# SCH_SEEK-998-001_v1_00.net
KiCad netlist of a schematic drawn in EasyEDA
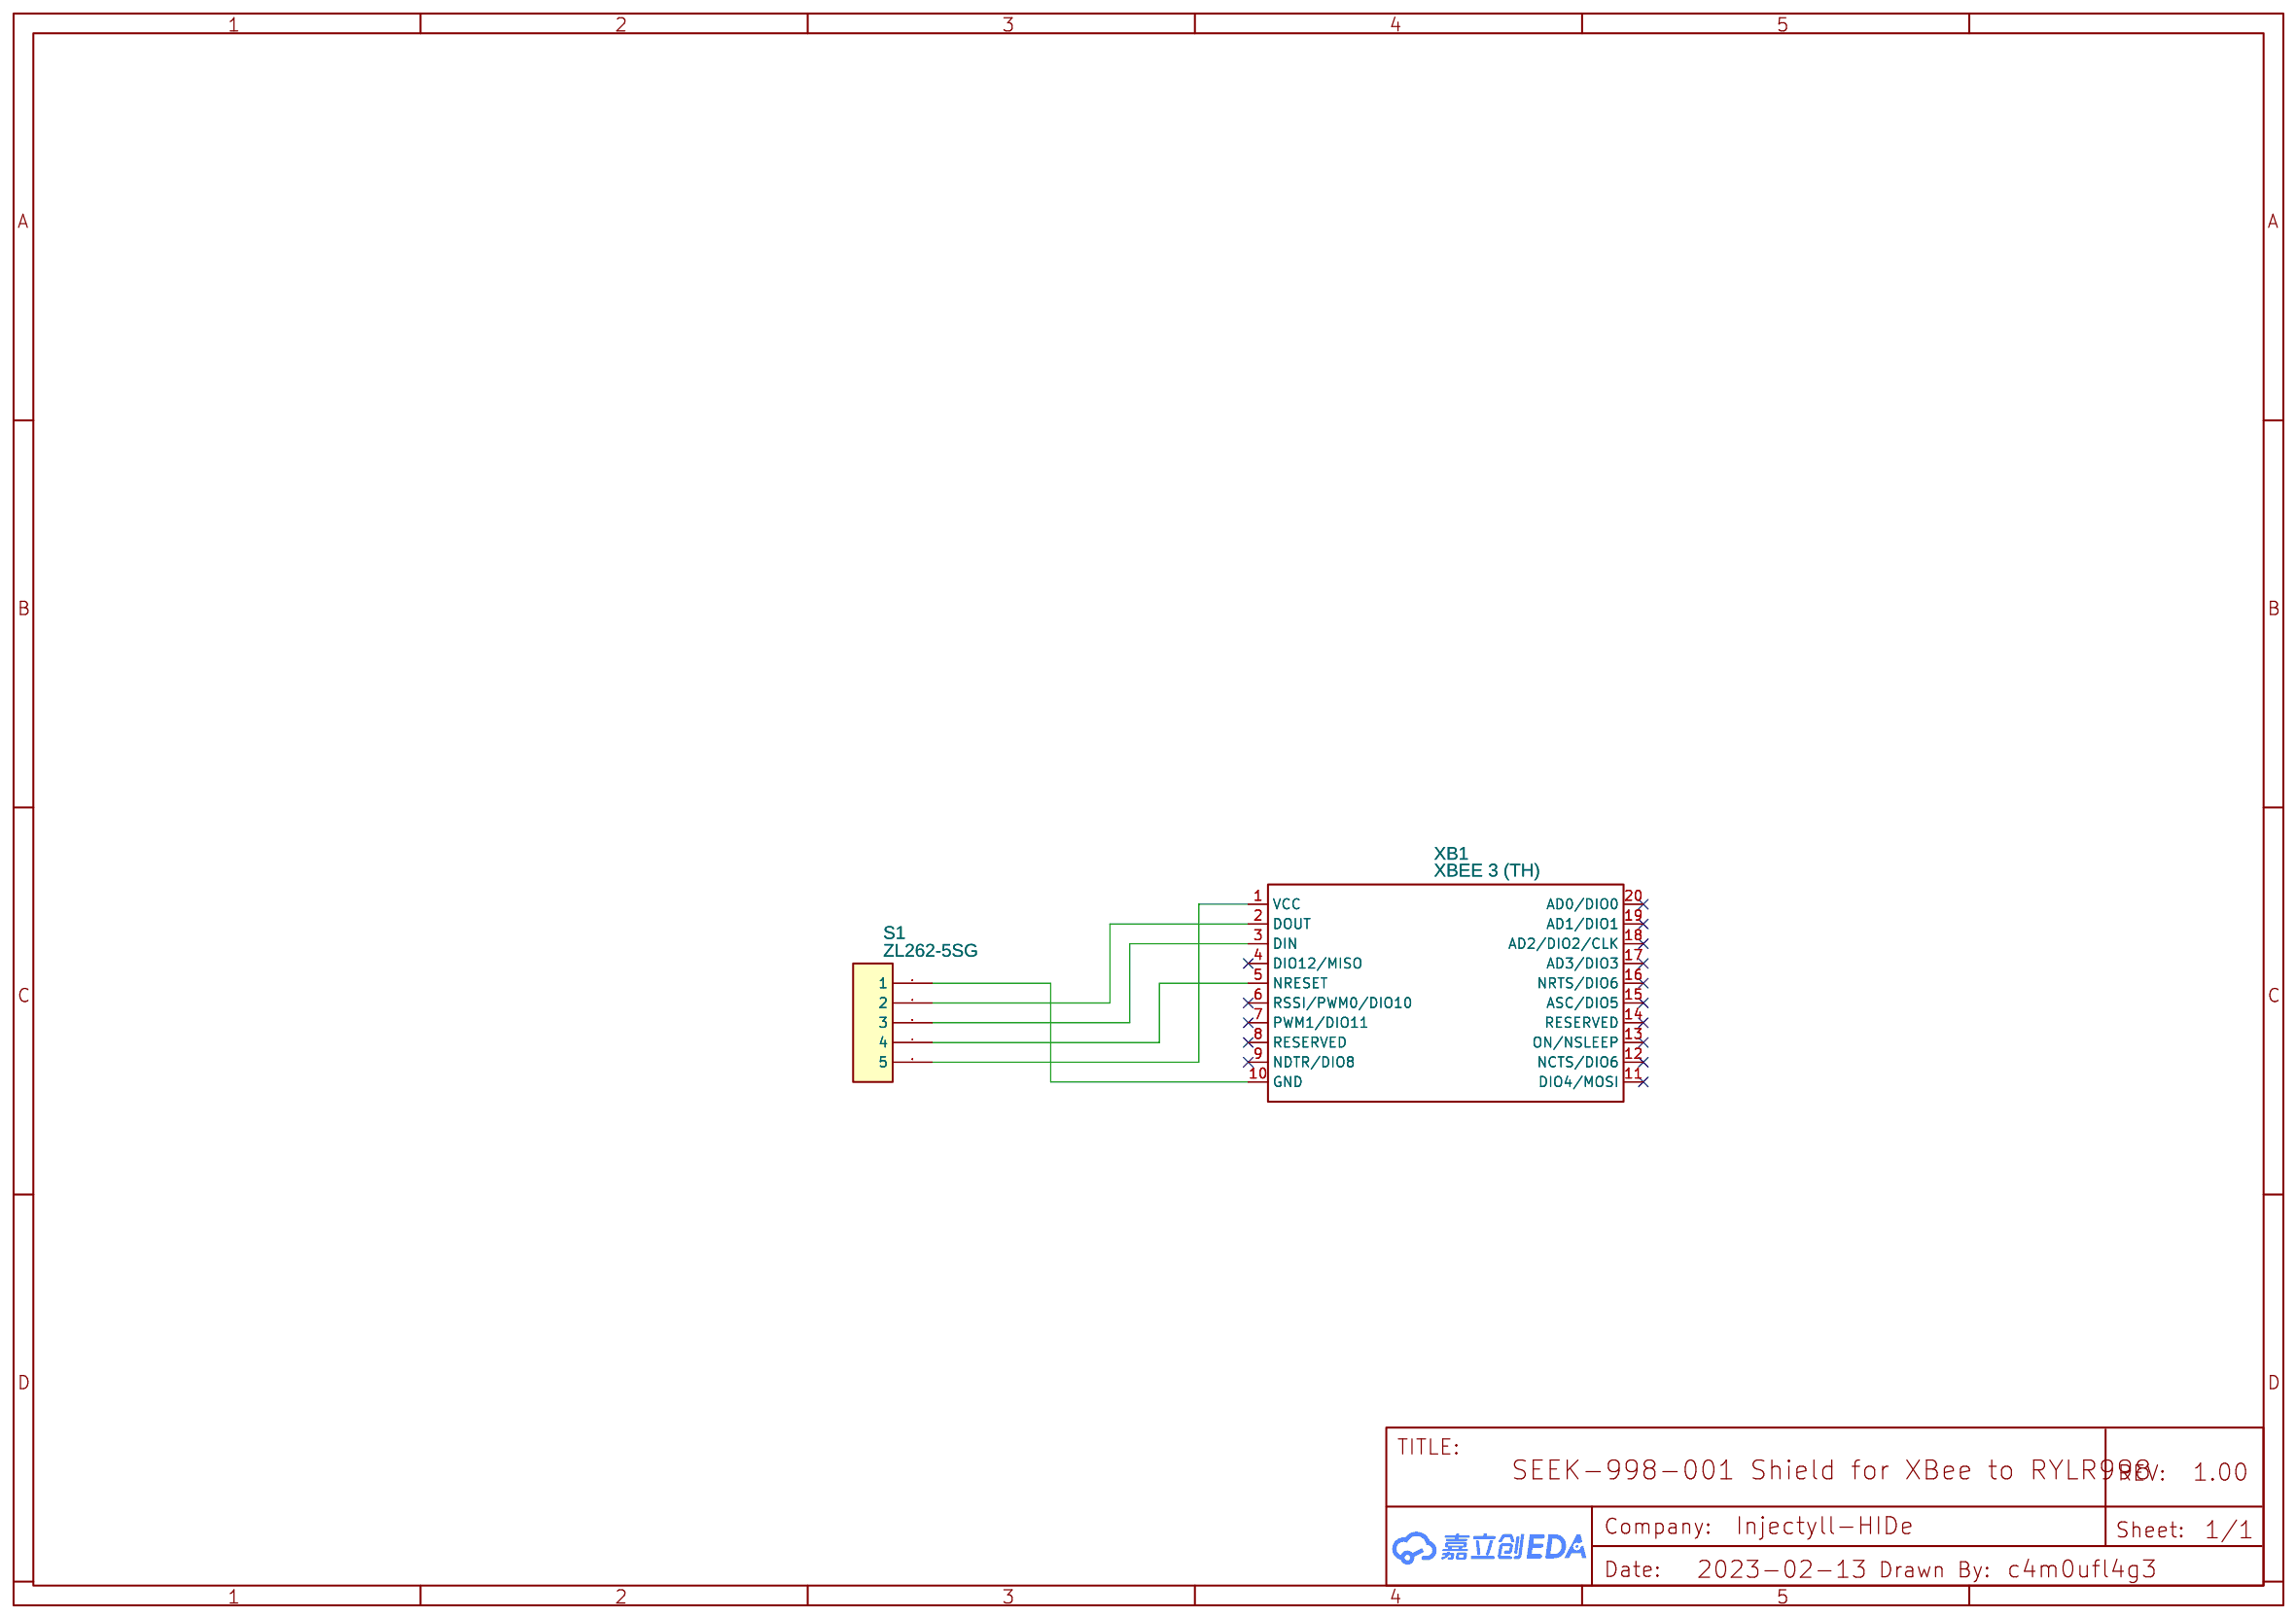
[diagram p0: schematic sheet]

(export (version "E")
  (design (tool "Eeschema 10.0.6"))
  (components
    (comp (ref "S1") (value "ZL262-5SG") (libsource (lib "") (part "ZL262-5SG")))
    (comp (ref "XB1") (value "XBEE 3 (TH)") (libsource (lib "") (part "XBEE 3 (TH)")))
  )
  (nets
    (net (code "1") (name "Net-(XB1-DIN)") (class "Default")
      (node (ref "S1") (pin "3") (pinfunction "3_3") (pintype "unspecified"))
      (node (ref "XB1") (pin "3") (pinfunction "DIN_3") (pintype "unspecified"))
    )
    (net (code "2") (name "Net-(XB1-DOUT)") (class "Default")
      (node (ref "S1") (pin "2") (pinfunction "2_2") (pintype "unspecified"))
      (node (ref "XB1") (pin "2") (pinfunction "DOUT_2") (pintype "unspecified"))
    )
    (net (code "3") (name "Net-(XB1-GND)") (class "Default")
      (node (ref "S1") (pin "1") (pinfunction "1_1") (pintype "unspecified"))
      (node (ref "XB1") (pin "10") (pinfunction "GND_10") (pintype "unspecified"))
    )
    (net (code "4") (name "Net-(XB1-NRESET)") (class "Default")
      (node (ref "S1") (pin "4") (pinfunction "4_4") (pintype "unspecified"))
      (node (ref "XB1") (pin "5") (pinfunction "NRESET_5") (pintype "unspecified"))
    )
    (net (code "5") (name "Net-(XB1-VCC)") (class "Default")
      (node (ref "S1") (pin "5") (pinfunction "5_5") (pintype "unspecified"))
      (node (ref "XB1") (pin "1") (pinfunction "VCC_1") (pintype "unspecified"))
    )
    (net (code "6") (name "unconnected-(XB1-AD0{slash}DIO0-Pad20)") (class "Default")
      (node (ref "XB1") (pin "20") (pinfunction "AD0/DIO0_20") (pintype "unspecified+no_connect"))
    )
    (net (code "7") (name "unconnected-(XB1-AD1{slash}DIO1-Pad19)") (class "Default")
      (node (ref "XB1") (pin "19") (pinfunction "AD1/DIO1_19") (pintype "unspecified+no_connect"))
    )
    (net (code "8") (name "unconnected-(XB1-AD2{slash}DIO2{slash}CLK-Pad18)") (class "Default")
      (node (ref "XB1") (pin "18") (pinfunction "AD2/DIO2/CLK_18") (pintype "unspecified+no_connect"))
    )
    (net (code "9") (name "unconnected-(XB1-AD3{slash}DIO3-Pad17)") (class "Default")
      (node (ref "XB1") (pin "17") (pinfunction "AD3/DIO3_17") (pintype "unspecified+no_connect"))
    )
    (net (code "10") (name "unconnected-(XB1-ASC{slash}DIO5-Pad15)") (class "Default")
      (node (ref "XB1") (pin "15") (pinfunction "ASC/DIO5_15") (pintype "unspecified+no_connect"))
    )
    (net (code "11") (name "unconnected-(XB1-DIO4{slash}MOSI-Pad11)") (class "Default")
      (node (ref "XB1") (pin "11") (pinfunction "DIO4/MOSI_11") (pintype "unspecified+no_connect"))
    )
    (net (code "12") (name "unconnected-(XB1-DIO12{slash}MISO-Pad4)") (class "Default")
      (node (ref "XB1") (pin "4") (pinfunction "DIO12/MISO_4") (pintype "unspecified+no_connect"))
    )
    (net (code "13") (name "unconnected-(XB1-NCTS{slash}DIO6-Pad12)") (class "Default")
      (node (ref "XB1") (pin "12") (pinfunction "NCTS/DIO6_12") (pintype "unspecified+no_connect"))
    )
    (net (code "14") (name "unconnected-(XB1-NDTR{slash}DIO8-Pad9)") (class "Default")
      (node (ref "XB1") (pin "9") (pinfunction "NDTR/DIO8_9") (pintype "unspecified+no_connect"))
    )
    (net (code "15") (name "unconnected-(XB1-NRTS{slash}DIO6-Pad16)") (class "Default")
      (node (ref "XB1") (pin "16") (pinfunction "NRTS/DIO6_16") (pintype "unspecified+no_connect"))
    )
    (net (code "16") (name "unconnected-(XB1-ON{slash}NSLEEP-Pad13)") (class "Default")
      (node (ref "XB1") (pin "13") (pinfunction "ON/NSLEEP_13") (pintype "unspecified+no_connect"))
    )
    (net (code "17") (name "unconnected-(XB1-PWM1{slash}DIO11-Pad7)") (class "Default")
      (node (ref "XB1") (pin "7") (pinfunction "PWM1/DIO11_7") (pintype "unspecified+no_connect"))
    )
    (net (code "18") (name "unconnected-(XB1-RESERVED-Pad8)") (class "Default")
      (node (ref "XB1") (pin "8") (pinfunction "RESERVED_8") (pintype "unspecified+no_connect"))
    )
    (net (code "19") (name "unconnected-(XB1-RESERVED-Pad14)") (class "Default")
      (node (ref "XB1") (pin "14") (pinfunction "RESERVED_14") (pintype "unspecified+no_connect"))
    )
    (net (code "20") (name "unconnected-(XB1-RSSI{slash}PWM0{slash}DIO10-Pad6)") (class "Default")
      (node (ref "XB1") (pin "6") (pinfunction "RSSI/PWM0/DIO10_6") (pintype "unspecified+no_connect"))
    )
  )
)
